# Lichtsensor.net
KiCad netlist of a schematic drawn in EAGLE
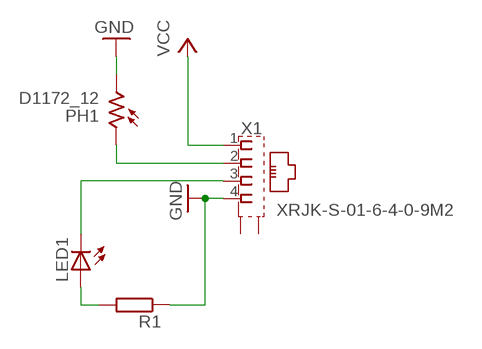
[diagram p0: schematic, sheet 1]

(export (version "E")
  (design (tool "Eeschema 10.0.6"))
  (components
    (comp (ref "LED1")
      (value "LED5MM")
      (footprint "eagle-import:LED5MM")
      (libsource (lib "eagle-import") (part "LED5MM"))
    )
    (comp (ref "PH1")
      (value "D1172_12")
      (footprint "eagle-import:D11XX")
      (libsource (lib "eagle-import") (part "D1172_12"))
    )
    (comp (ref "R1")
      (value "R-EU_0207/10")
      (footprint "eagle-import:0207_10")
      (libsource (lib "eagle-import") (part "R-EU_0207/10"))
    )
    (comp (ref "X1")
      (value "XRJK-S-01-6-4-0-9M2")
      (footprint "eagle-import:XRJK-S-01-6-4-0-9M2")
      (libsource (lib "eagle-import") (part "XRJK4-0-9M2-S-01-6-"))
    )
  )
  (nets
    (net (code "1") (name "GND") (class "Default")
      (node (ref "PH1") (pin "2") (pinfunction "2_2") (pintype "passive"))
      (node (ref "R1") (pin "1") (pinfunction "1_1") (pintype "passive"))
      (node (ref "X1") (pin "4") (pinfunction "4_4") (pintype "passive"))
    )
    (net (code "2") (name "Net-(LED1-C)") (class "Default")
      (node (ref "LED1") (pin "K") (pinfunction "C_K") (pintype "passive"))
      (node (ref "X1") (pin "3") (pinfunction "3_3") (pintype "passive"))
    )
    (net (code "3") (name "Net-(LED1-PadA)") (class "Default")
      (node (ref "LED1") (pin "A") (pinfunction "A_A") (pintype "passive"))
      (node (ref "R1") (pin "2") (pinfunction "2_2") (pintype "passive"))
    )
    (net (code "4") (name "Net-(PH1-Pad1)") (class "Default")
      (node (ref "PH1") (pin "1") (pinfunction "1_1") (pintype "passive"))
      (node (ref "X1") (pin "2") (pinfunction "2_2") (pintype "passive"))
    )
    (net (code "5") (name "VCC") (class "Default")
      (node (ref "X1") (pin "1") (pinfunction "1_1") (pintype "passive"))
    )
    (net (code "6") (name "unconnected-(X1-S-PadS1)") (class "Default")
      (node (ref "X1") (pin "S1") (pinfunction "S_S1") (pintype "passive"))
    )
    (net (code "7") (name "unconnected-(X1-S-PadS2)") (class "Default")
      (node (ref "X1") (pin "S2") (pinfunction "S_S2") (pintype "passive"))
    )
  )
)
